# PowerShield_v1-0.net
KiCad netlist of a schematic drawn in EAGLE
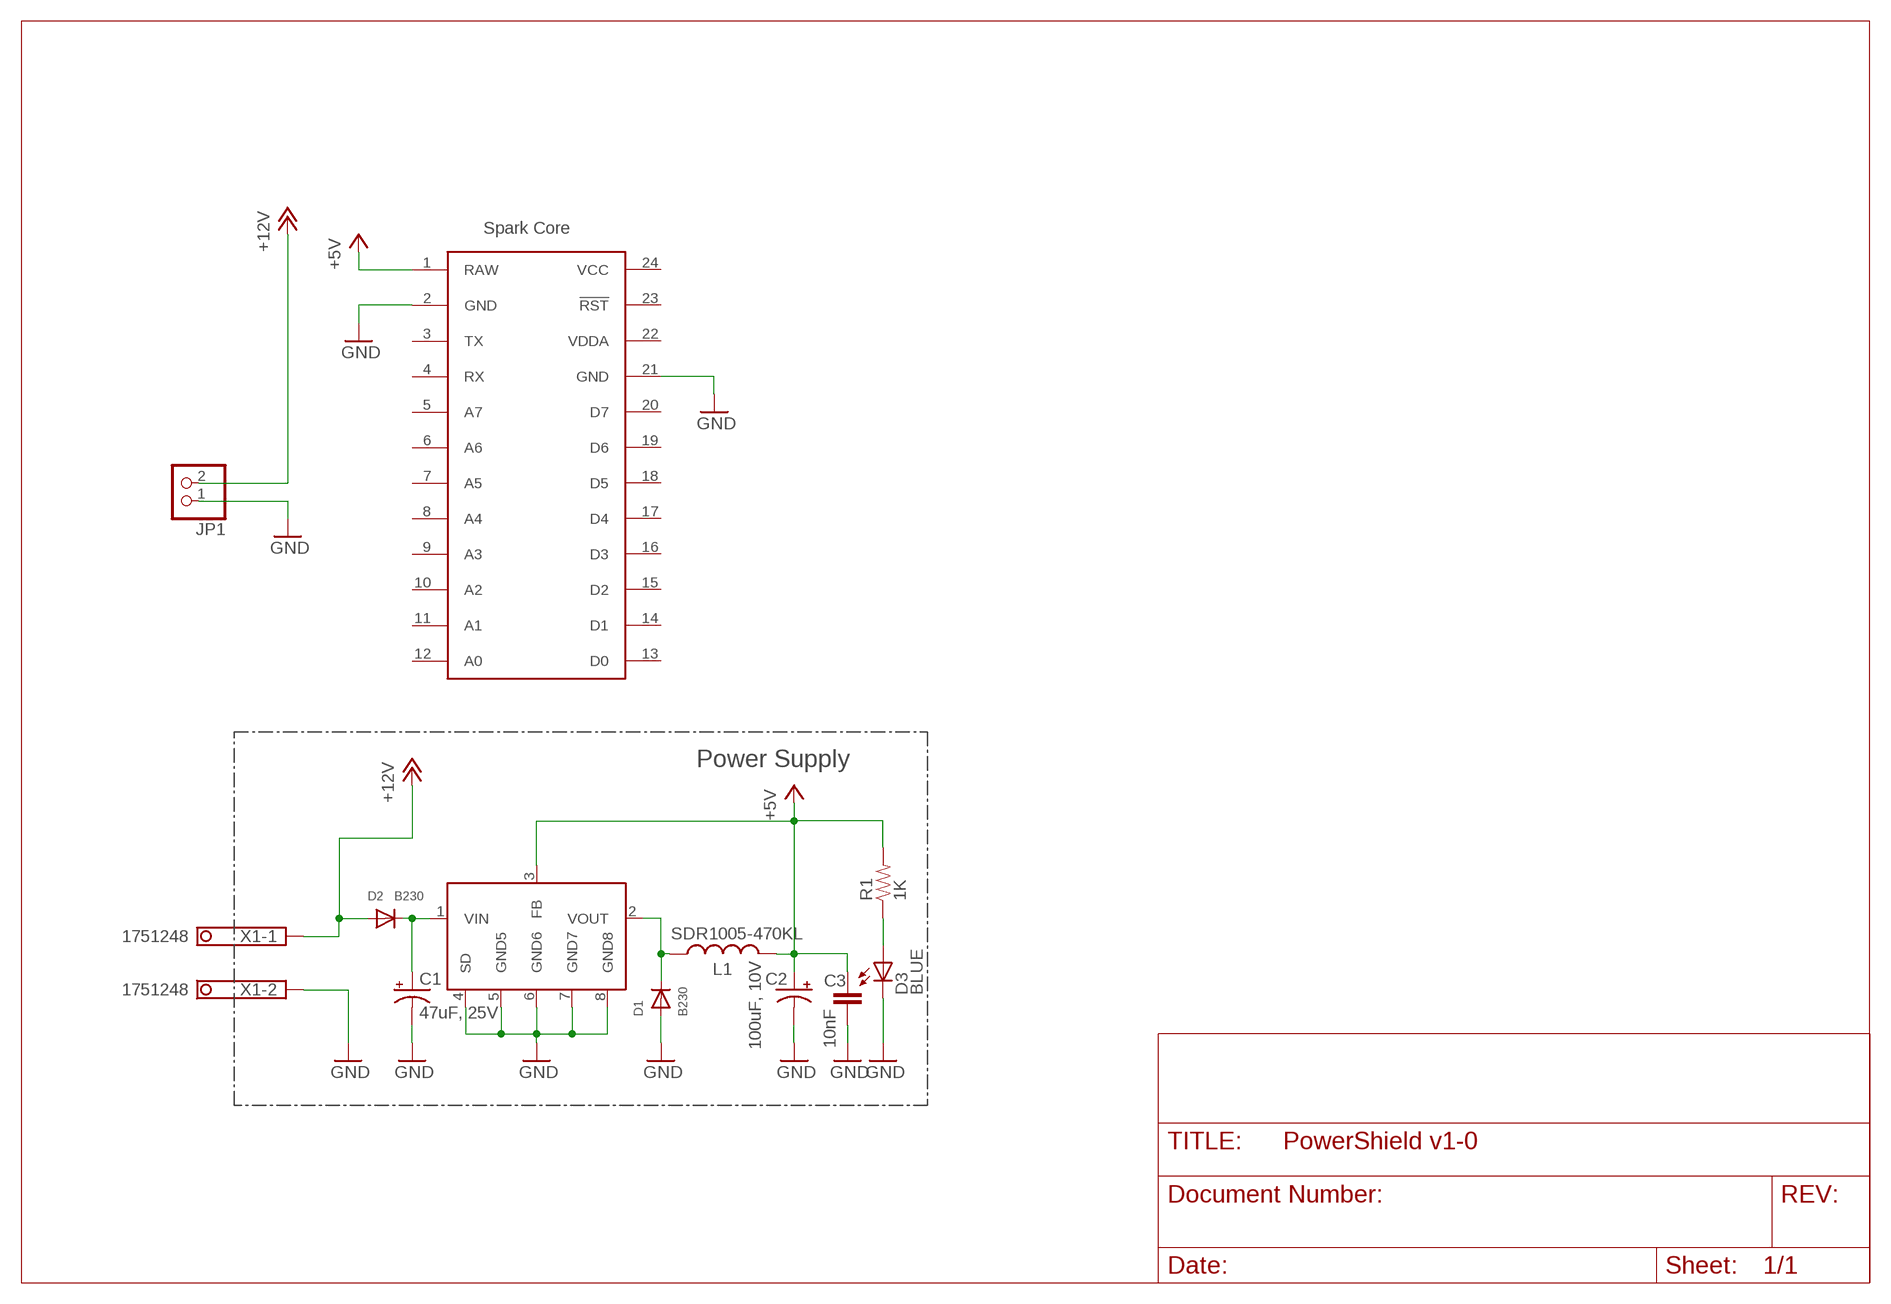
[diagram p0: schematic, sheet 1]

(export (version "E")
  (design (tool "Eeschema 10.0.6"))
  (components
    (comp (ref "C1")
      (value "47uF, 25V")
      (footprint "eagle-import:PANASONIC_D")
      (libsource (lib "eagle-import") (part "CAP_POLD"))
    )
    (comp (ref "C2")
      (value "100uF, 10V")
      (footprint "eagle-import:PANASONIC_D")
      (libsource (lib "eagle-import") (part "CAP_POLD"))
    )
    (comp (ref "C3")
      (value "10nF")
      (footprint "eagle-import:0603-CAP")
      (libsource (lib "eagle-import") (part "CAP0603-CAP"))
    )
    (comp (ref "D1")
      (value "B230")
      (footprint "eagle-import:SMADIODE")
      (libsource (lib "eagle-import") (part "DIODESMA"))
    )
    (comp (ref "D2")
      (value "B230")
      (footprint "eagle-import:SMADIODE")
      (libsource (lib "eagle-import") (part "DIODESMA"))
    )
    (comp (ref "D3")
      (value "BLUE")
      (footprint "eagle-import:LED-0603")
      (libsource (lib "eagle-import") (part "LED0603"))
    )
    (comp (ref "JP1")
      (value "PINHD-1X2")
      (footprint "eagle-import:1X02")
      (libsource (lib "eagle-import") (part "PINHD-1X2"))
    )
    (comp (ref "L1")
      (value "SDR1005-470KL")
      (footprint "eagle-import:INDUCTOR-SDR1005-470KL")
      (libsource (lib "eagle-import") (part "INDUCTOR-SPARKFUN"))
    )
    (comp (ref "R1")
      (value "1K")
      (footprint "eagle-import:0603-RES")
      (libsource (lib "eagle-import") (part "RESISTOR0603-RES"))
    )
    (comp (ref "U$2")
      (value "SPARK_CORECORE")
      (footprint "eagle-import:SPARK_CORE")
      (libsource (lib "eagle-import") (part "SPARK_CORECORE"))
    )
    (comp (ref "U1")
      (value "AP1509-50SG-13")
      (footprint "eagle-import:SO08")
      (libsource (lib "eagle-import") (part "AP1509-50SG-13"))
    )
    (comp (ref "X1")
      (value "1751248")
      (footprint "eagle-import:1751248")
      (libsource (lib "eagle-import") (part "1751248"))
    )
  )
  (nets
    (net (code "1") (name "+5V") (class "Default")
      (node (ref "C2") (pin "+") (pinfunction "+_+") (pintype "passive"))
      (node (ref "C3") (pin "2") (pinfunction "2_2") (pintype "passive"))
      (node (ref "L1") (pin "P$2") (pinfunction "2_P$2") (pintype "passive"))
      (node (ref "R1") (pin "2") (pinfunction "2_2") (pintype "passive"))
      (node (ref "U$2") (pin "1") (pinfunction "RAW_1") (pintype "power_in"))
      (node (ref "U1") (pin "3") (pinfunction "FB_3") (pintype "bidirectional"))
    )
    (net (code "2") (name "+12V") (class "Default")
      (node (ref "D2") (pin "A") (pinfunction "A_A") (pintype "passive"))
      (node (ref "JP1") (pin "2") (pinfunction "2_2") (pintype "passive"))
      (node (ref "X1") (pin "1") (pinfunction "K_1") (pintype "passive"))
    )
    (net (code "3") (name "/VCC") (class "Default")
      (node (ref "U$2") (pin "24") (pinfunction "VCC_24") (pintype "power_in"))
    )
    (net (code "4") (name "/VDDA") (class "Default")
      (node (ref "U$2") (pin "22") (pinfunction "VDDA_22") (pintype "power_in"))
    )
    (net (code "5") (name "GND") (class "Default")
      (node (ref "C1") (pin "-") (pinfunction "-_-") (pintype "passive"))
      (node (ref "C2") (pin "-") (pinfunction "-_-") (pintype "passive"))
      (node (ref "C3") (pin "1") (pinfunction "1_1") (pintype "passive"))
      (node (ref "D1") (pin "A") (pinfunction "A_A") (pintype "passive"))
      (node (ref "D3") (pin "C") (pinfunction "C_C") (pintype "passive"))
      (node (ref "JP1") (pin "1") (pinfunction "1_1") (pintype "passive"))
      (node (ref "U$2") (pin "2") (pinfunction "GND_2") (pintype "power_in"))
      (node (ref "U$2") (pin "21") (pinfunction "GND_21") (pintype "power_in"))
      (node (ref "U1") (pin "4") (pinfunction "SD_4") (pintype "bidirectional"))
      (node (ref "U1") (pin "5") (pinfunction "GND5_5") (pintype "bidirectional"))
      (node (ref "U1") (pin "6") (pinfunction "GND6_6") (pintype "bidirectional"))
      (node (ref "U1") (pin "7") (pinfunction "GND7_7") (pintype "bidirectional"))
      (node (ref "U1") (pin "8") (pinfunction "GND8_8") (pintype "bidirectional"))
      (node (ref "X1") (pin "2") (pinfunction "K_2") (pintype "passive"))
    )
    (net (code "6") (name "Net-(D3-PadA)") (class "Default")
      (node (ref "D3") (pin "A") (pinfunction "A_A") (pintype "passive"))
      (node (ref "R1") (pin "1") (pinfunction "1_1") (pintype "passive"))
    )
    (net (code "7") (name "Net-(L1-1)") (class "Default")
      (node (ref "D1") (pin "C") (pinfunction "C_C") (pintype "passive"))
      (node (ref "L1") (pin "P$1") (pinfunction "1_P$1") (pintype "passive"))
      (node (ref "U1") (pin "2") (pinfunction "VOUT_2") (pintype "bidirectional"))
    )
    (net (code "8") (name "Net-(U1-VIN)") (class "Default")
      (node (ref "C1") (pin "+") (pinfunction "+_+") (pintype "passive"))
      (node (ref "D2") (pin "C") (pinfunction "C_C") (pintype "passive"))
      (node (ref "U1") (pin "1") (pinfunction "VIN_1") (pintype "bidirectional"))
    )
    (net (code "9") (name "unconnected-(U$2-A0-Pad12)") (class "Default")
      (node (ref "U$2") (pin "12") (pinfunction "A0_12") (pintype "bidirectional"))
    )
    (net (code "10") (name "unconnected-(U$2-A1-Pad11)") (class "Default")
      (node (ref "U$2") (pin "11") (pinfunction "A1_11") (pintype "bidirectional"))
    )
    (net (code "11") (name "unconnected-(U$2-A2-Pad10)") (class "Default")
      (node (ref "U$2") (pin "10") (pinfunction "A2_10") (pintype "bidirectional"))
    )
    (net (code "12") (name "unconnected-(U$2-A3-Pad9)") (class "Default")
      (node (ref "U$2") (pin "9") (pinfunction "A3_9") (pintype "bidirectional"))
    )
    (net (code "13") (name "unconnected-(U$2-A4-Pad8)") (class "Default")
      (node (ref "U$2") (pin "8") (pinfunction "A4_8") (pintype "bidirectional"))
    )
    (net (code "14") (name "unconnected-(U$2-A5-Pad7)") (class "Default")
      (node (ref "U$2") (pin "7") (pinfunction "A5_7") (pintype "bidirectional"))
    )
    (net (code "15") (name "unconnected-(U$2-A6-Pad6)") (class "Default")
      (node (ref "U$2") (pin "6") (pinfunction "A6_6") (pintype "bidirectional"))
    )
    (net (code "16") (name "unconnected-(U$2-A7-Pad5)") (class "Default")
      (node (ref "U$2") (pin "5") (pinfunction "A7_5") (pintype "bidirectional"))
    )
    (net (code "17") (name "unconnected-(U$2-D0-Pad13)") (class "Default")
      (node (ref "U$2") (pin "13") (pinfunction "D0_13") (pintype "bidirectional"))
    )
    (net (code "18") (name "unconnected-(U$2-D1-Pad14)") (class "Default")
      (node (ref "U$2") (pin "14") (pinfunction "D1_14") (pintype "bidirectional"))
    )
    (net (code "19") (name "unconnected-(U$2-D2-Pad15)") (class "Default")
      (node (ref "U$2") (pin "15") (pinfunction "D2_15") (pintype "bidirectional"))
    )
    (net (code "20") (name "unconnected-(U$2-D3-Pad16)") (class "Default")
      (node (ref "U$2") (pin "16") (pinfunction "D3_16") (pintype "bidirectional"))
    )
    (net (code "21") (name "unconnected-(U$2-D4-Pad17)") (class "Default")
      (node (ref "U$2") (pin "17") (pinfunction "D4_17") (pintype "bidirectional"))
    )
    (net (code "22") (name "unconnected-(U$2-D5-Pad18)") (class "Default")
      (node (ref "U$2") (pin "18") (pinfunction "D5_18") (pintype "bidirectional"))
    )
    (net (code "23") (name "unconnected-(U$2-D6-Pad19)") (class "Default")
      (node (ref "U$2") (pin "19") (pinfunction "D6_19") (pintype "bidirectional"))
    )
    (net (code "24") (name "unconnected-(U$2-D7-Pad20)") (class "Default")
      (node (ref "U$2") (pin "20") (pinfunction "D7_20") (pintype "bidirectional"))
    )
    (net (code "25") (name "unconnected-(U$2-RX-Pad4)") (class "Default")
      (node (ref "U$2") (pin "4") (pinfunction "RX_4") (pintype "bidirectional"))
    )
    (net (code "26") (name "unconnected-(U$2-TX-Pad3)") (class "Default")
      (node (ref "U$2") (pin "3") (pinfunction "TX_3") (pintype "bidirectional"))
    )
    (net (code "27") (name "unconnected-(U$2-~{RST}-Pad23)") (class "Default")
      (node (ref "U$2") (pin "23") (pinfunction "~{RST}_23") (pintype "bidirectional"))
    )
  )
)
